# helical.net
KiCad netlist of a schematic drawn in Altium Designer
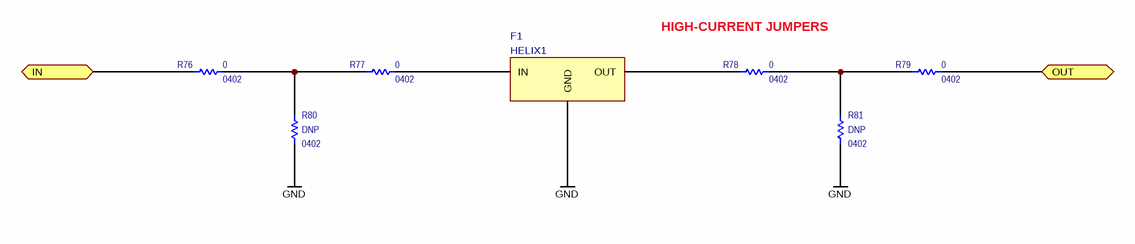
[diagram p0: helical.SchDoc]

(export (version "E")
  (design (tool "Eeschema 10.0.6"))
  (components
    (comp (ref "F1")
      (value "HELIX1")
      (footprint "HELIX1")
      (description "Helical Filter 915MHz")
      (fields (field (name "MANUFACTURER") "Signal Laboratories"))
      (libsource (lib "siglabs") (part "HELIX1"))
    )
    (comp (ref "R76")
      (value "0")
      (footprint "generic:RESC1005X40N")
      (description "High Current Jumper Chip Resistor 0402")
      (fields
        (field (name "PACKAGE") "0402")
        (field (name "MANUFACTURER") "Stackpole Electronics")
        (field (name "Comment") "HCJ0402ZT0R00")
      )
      (libsource (lib "Graviton") (part "RES 0603"))
    )
    (comp (ref "R77")
      (value "0")
      (footprint "generic:RESC1005X40N")
      (description "High Current Jumper Chip Resistor 0402")
      (fields
        (field (name "PACKAGE") "0402")
        (field (name "MANUFACTURER") "Stackpole Electronics")
        (field (name "Comment") "HCJ0402ZT0R00")
      )
      (libsource (lib "Graviton") (part "RES 0603"))
    )
    (comp (ref "R78")
      (value "0")
      (footprint "generic:RESC1005X40N")
      (description "High Current Jumper Chip Resistor 0402")
      (fields
        (field (name "PACKAGE") "0402")
        (field (name "MANUFACTURER") "Stackpole Electronics")
        (field (name "Comment") "HCJ0402ZT0R00")
      )
      (libsource (lib "Graviton") (part "RES 0603"))
    )
    (comp (ref "R79")
      (value "0")
      (footprint "generic:RESC1005X40N")
      (description "High Current Jumper Chip Resistor 0402")
      (fields
        (field (name "PACKAGE") "0402")
        (field (name "MANUFACTURER") "Stackpole Electronics")
        (field (name "Comment") "HCJ0402ZT0R00")
      )
      (libsource (lib "Graviton") (part "RES 0603"))
    )
    (comp (ref "R80")
      (value "HCJ0402ZT0R00")
      (footprint "generic:RESC1005X40N")
      (description "High Current Jumper Chip Resistor 0402")
      (fields
        (field (name "PACKAGE") "0402")
        (field (name "MANUFACTURER") "Stackpole Electronics")
        (field (name "DO NOT PLACE") "DNP")
      )
      (libsource (lib "Graviton") (part "RES 0603"))
    )
    (comp (ref "R81")
      (value "HCJ0402ZT0R00")
      (footprint "generic:RESC1005X40N")
      (description "High Current Jumper Chip Resistor 0402")
      (fields
        (field (name "PACKAGE") "0402")
        (field (name "MANUFACTURER") "Stackpole Electronics")
        (field (name "DO NOT PLACE") "DNP")
      )
      (libsource (lib "Graviton") (part "RES 0603"))
    )
  )
  (nets
    (net (code "1") (name "/IN") (class "Default")
      (node (ref "R76") (pin "2") (pinfunction "2_2") (pintype "passive"))
    )
    (net (code "2") (name "/OUT") (class "Default")
      (node (ref "R79") (pin "1") (pinfunction "1_1") (pintype "passive"))
    )
    (net (code "3") (name "GND") (class "Default")
      (node (ref "F1") (pin "GND") (pinfunction "GND_GND") (pintype "passive"))
      (node (ref "R80") (pin "2") (pinfunction "2_2") (pintype "passive"))
      (node (ref "R81") (pin "2") (pinfunction "2_2") (pintype "passive"))
    )
    (net (code "4") (name "Net-(F1-PadIN)") (class "Default")
      (node (ref "F1") (pin "IN") (pinfunction "IN_IN") (pintype "passive"))
      (node (ref "R77") (pin "1") (pinfunction "1_1") (pintype "passive"))
    )
    (net (code "5") (name "Net-(F1-PadOUT)") (class "Default")
      (node (ref "F1") (pin "OUT") (pinfunction "OUT_OUT") (pintype "passive"))
      (node (ref "R78") (pin "2") (pinfunction "2_2") (pintype "passive"))
    )
    (net (code "6") (name "Net-(R76-Pad1)") (class "Default")
      (node (ref "R76") (pin "1") (pinfunction "1_1") (pintype "passive"))
      (node (ref "R77") (pin "2") (pinfunction "2_2") (pintype "passive"))
      (node (ref "R80") (pin "1") (pinfunction "1_1") (pintype "passive"))
    )
    (net (code "7") (name "Net-(R78-Pad1)") (class "Default")
      (node (ref "R78") (pin "1") (pinfunction "1_1") (pintype "passive"))
      (node (ref "R79") (pin "2") (pinfunction "2_2") (pintype "passive"))
      (node (ref "R81") (pin "1") (pinfunction "1_1") (pintype "passive"))
    )
  )
)
